# MIT_SRAM.net
KiCad netlist of a schematic drawn in EAGLE
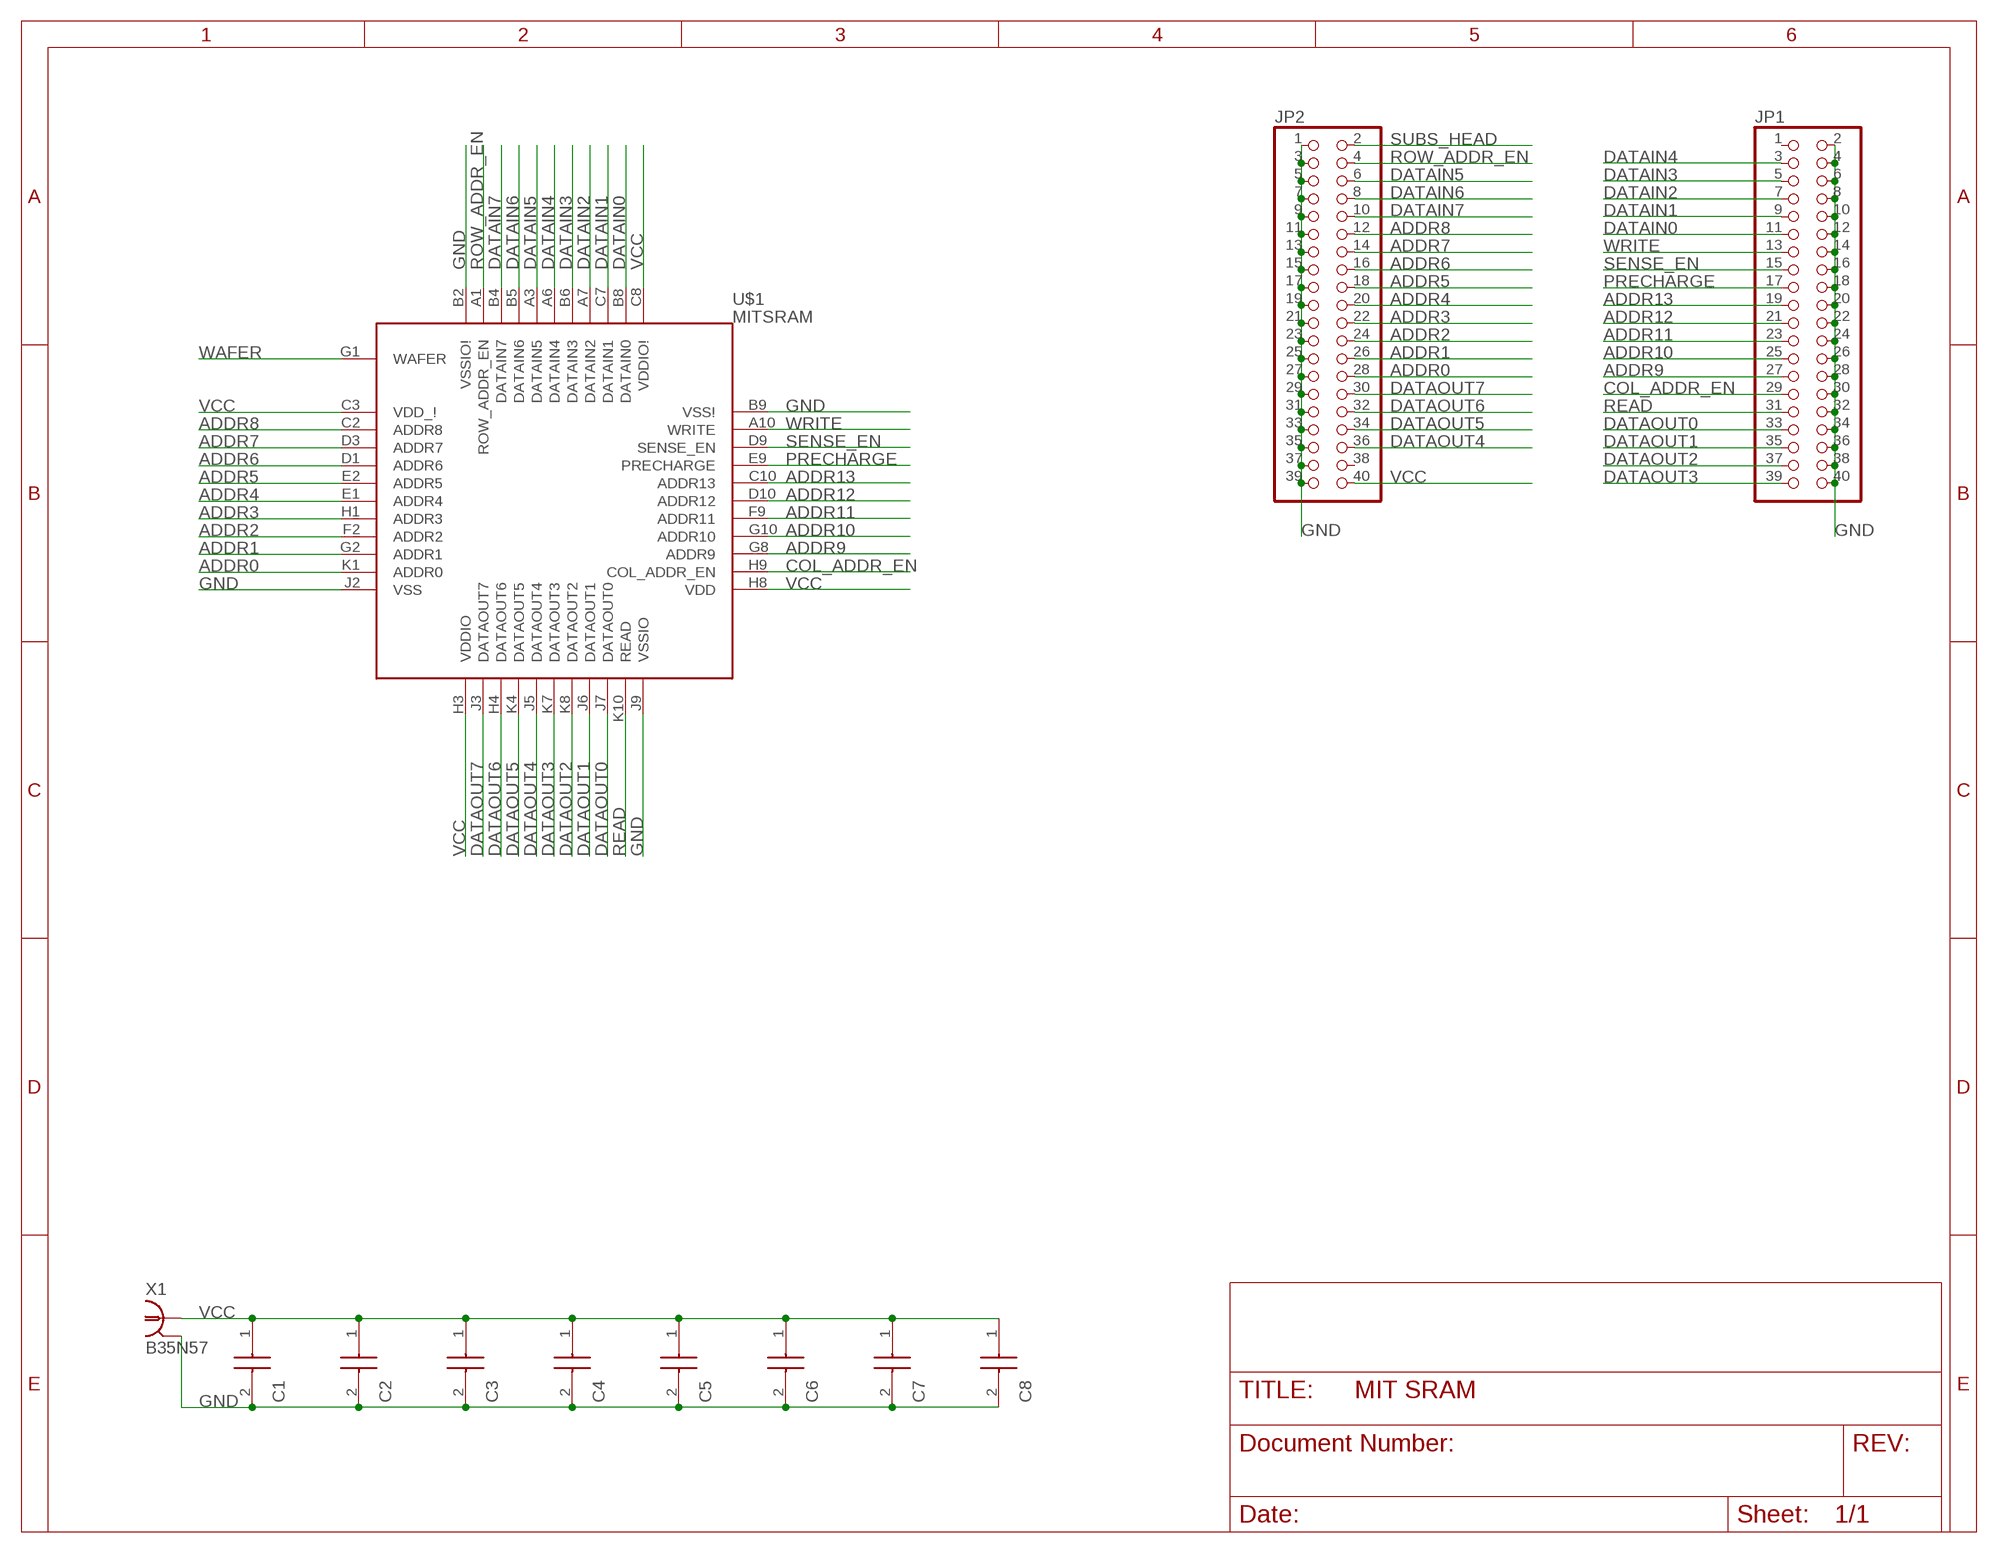
[diagram p0: schematic, sheet 1]

(export (version "E")
  (design (tool "Eeschema 10.0.6"))
  (components
    (comp (ref "C1")
      (value "K104K15X7RF53H5")
      (footprint "eagle-import:K104K15X7RF53H5")
      (fields
        (field (name "MOUSER_PART_NUMBER") "594-K104K15X7RF53H5")
        (field (name "RS_PART_NUMBER") "8523270")
      )
      (libsource (lib "eagle-import") (part "K104K15X7RF53H5"))
    )
    (comp (ref "C2")
      (value "K104K15X7RF53H5")
      (footprint "eagle-import:K104K15X7RF53H5")
      (fields
        (field (name "MOUSER_PART_NUMBER") "594-K104K15X7RF53H5")
        (field (name "RS_PART_NUMBER") "8523270")
      )
      (libsource (lib "eagle-import") (part "K104K15X7RF53H5"))
    )
    (comp (ref "C3")
      (value "K104K15X7RF53H5")
      (footprint "eagle-import:K104K15X7RF53H5")
      (fields
        (field (name "MOUSER_PART_NUMBER") "594-K104K15X7RF53H5")
        (field (name "RS_PART_NUMBER") "8523270")
      )
      (libsource (lib "eagle-import") (part "K104K15X7RF53H5"))
    )
    (comp (ref "C4")
      (value "K104K15X7RF53H5")
      (footprint "eagle-import:K104K15X7RF53H5")
      (fields
        (field (name "MOUSER_PART_NUMBER") "594-K104K15X7RF53H5")
        (field (name "RS_PART_NUMBER") "8523270")
      )
      (libsource (lib "eagle-import") (part "K104K15X7RF53H5"))
    )
    (comp (ref "C5")
      (value "K104K15X7RF53H5")
      (footprint "eagle-import:K104K15X7RF53H5")
      (fields
        (field (name "MOUSER_PART_NUMBER") "594-K104K15X7RF53H5")
        (field (name "RS_PART_NUMBER") "8523270")
      )
      (libsource (lib "eagle-import") (part "K104K15X7RF53H5"))
    )
    (comp (ref "C6")
      (value "K104K15X7RF53H5")
      (footprint "eagle-import:K104K15X7RF53H5")
      (fields
        (field (name "MOUSER_PART_NUMBER") "594-K104K15X7RF53H5")
        (field (name "RS_PART_NUMBER") "8523270")
      )
      (libsource (lib "eagle-import") (part "K104K15X7RF53H5"))
    )
    (comp (ref "C7")
      (value "K104K15X7RF53H5")
      (footprint "eagle-import:K104K15X7RF53H5")
      (fields
        (field (name "MOUSER_PART_NUMBER") "594-K104K15X7RF53H5")
        (field (name "RS_PART_NUMBER") "8523270")
      )
      (libsource (lib "eagle-import") (part "K104K15X7RF53H5"))
    )
    (comp (ref "C8")
      (value "K104K15X7RF53H5")
      (footprint "eagle-import:K104K15X7RF53H5")
      (fields
        (field (name "MOUSER_PART_NUMBER") "594-K104K15X7RF53H5")
        (field (name "RS_PART_NUMBER") "8523270")
      )
      (libsource (lib "eagle-import") (part "K104K15X7RF53H5"))
    )
    (comp (ref "JP1")
      (value "PINHD-2X20")
      (footprint "eagle-import:2X20")
      (libsource (lib "eagle-import") (part "PINHD-2X20"))
    )
    (comp (ref "JP2")
      (value "PINHD-2X20")
      (footprint "eagle-import:2X20")
      (libsource (lib "eagle-import") (part "PINHD-2X20"))
    )
    (comp (ref "U$1")
      (value "MITSRAM")
      (footprint "eagle-import:BGA100C50P10X10_600X600X100N")
      (libsource (lib "eagle-import") (part "MITSRAM"))
    )
    (comp (ref "X1")
      (value "B35N57")
      (footprint "eagle-import:B35N57")
      (libsource (lib "eagle-import") (part "B35N57"))
    )
  )
  (nets
    (net (code "1") (name "/ADDR0") (class "Default")
      (node (ref "JP2") (pin "28") (pinfunction "28_28") (pintype "passive"))
      (node (ref "U$1") (pin "K1") (pinfunction "ADDR0_K1") (pintype "bidirectional"))
    )
    (net (code "2") (name "/ADDR1") (class "Default")
      (node (ref "JP2") (pin "26") (pinfunction "26_26") (pintype "passive"))
      (node (ref "U$1") (pin "G2") (pinfunction "ADDR1_G2") (pintype "bidirectional"))
    )
    (net (code "3") (name "/ADDR2") (class "Default")
      (node (ref "JP2") (pin "24") (pinfunction "24_24") (pintype "passive"))
      (node (ref "U$1") (pin "F2") (pinfunction "ADDR2_F2") (pintype "bidirectional"))
    )
    (net (code "4") (name "/ADDR3") (class "Default")
      (node (ref "JP2") (pin "22") (pinfunction "22_22") (pintype "passive"))
      (node (ref "U$1") (pin "H1") (pinfunction "ADDR3_H1") (pintype "bidirectional"))
    )
    (net (code "5") (name "/ADDR4") (class "Default")
      (node (ref "JP2") (pin "20") (pinfunction "20_20") (pintype "passive"))
      (node (ref "U$1") (pin "E1") (pinfunction "ADDR4_E1") (pintype "bidirectional"))
    )
    (net (code "6") (name "/ADDR5") (class "Default")
      (node (ref "JP2") (pin "18") (pinfunction "18_18") (pintype "passive"))
      (node (ref "U$1") (pin "E2") (pinfunction "ADDR5_E2") (pintype "bidirectional"))
    )
    (net (code "7") (name "/ADDR6") (class "Default")
      (node (ref "JP2") (pin "16") (pinfunction "16_16") (pintype "passive"))
      (node (ref "U$1") (pin "D1") (pinfunction "ADDR6_D1") (pintype "bidirectional"))
    )
    (net (code "8") (name "/ADDR7") (class "Default")
      (node (ref "JP2") (pin "14") (pinfunction "14_14") (pintype "passive"))
      (node (ref "U$1") (pin "D3") (pinfunction "ADDR7_D3") (pintype "bidirectional"))
    )
    (net (code "9") (name "/ADDR8") (class "Default")
      (node (ref "JP2") (pin "12") (pinfunction "12_12") (pintype "passive"))
      (node (ref "U$1") (pin "C2") (pinfunction "ADDR8_C2") (pintype "bidirectional"))
    )
    (net (code "10") (name "/ADDR9") (class "Default")
      (node (ref "JP1") (pin "27") (pinfunction "27_27") (pintype "passive"))
      (node (ref "U$1") (pin "G8") (pinfunction "ADDR9_G8") (pintype "bidirectional"))
    )
    (net (code "11") (name "/ADDR10") (class "Default")
      (node (ref "JP1") (pin "25") (pinfunction "25_25") (pintype "passive"))
      (node (ref "U$1") (pin "G10") (pinfunction "ADDR10_G10") (pintype "bidirectional"))
    )
    (net (code "12") (name "/ADDR11") (class "Default")
      (node (ref "JP1") (pin "23") (pinfunction "23_23") (pintype "passive"))
      (node (ref "U$1") (pin "F9") (pinfunction "ADDR11_F9") (pintype "bidirectional"))
    )
    (net (code "13") (name "/ADDR12") (class "Default")
      (node (ref "JP1") (pin "21") (pinfunction "21_21") (pintype "passive"))
      (node (ref "U$1") (pin "D10") (pinfunction "ADDR12_D10") (pintype "bidirectional"))
    )
    (net (code "14") (name "/ADDR13") (class "Default")
      (node (ref "JP1") (pin "19") (pinfunction "19_19") (pintype "passive"))
      (node (ref "U$1") (pin "C10") (pinfunction "ADDR13_C10") (pintype "bidirectional"))
    )
    (net (code "15") (name "/COL_ADDR_EN") (class "Default")
      (node (ref "JP1") (pin "29") (pinfunction "29_29") (pintype "passive"))
      (node (ref "U$1") (pin "H9") (pinfunction "COL_ADDR_EN_H9") (pintype "bidirectional"))
    )
    (net (code "16") (name "/DATAIN0") (class "Default")
      (node (ref "JP1") (pin "11") (pinfunction "11_11") (pintype "passive"))
      (node (ref "U$1") (pin "B8") (pinfunction "DATAIN0_B8") (pintype "bidirectional"))
    )
    (net (code "17") (name "/DATAIN1") (class "Default")
      (node (ref "JP1") (pin "9") (pinfunction "9_9") (pintype "passive"))
      (node (ref "U$1") (pin "C7") (pinfunction "DATAIN1_C7") (pintype "bidirectional"))
    )
    (net (code "18") (name "/DATAIN2") (class "Default")
      (node (ref "JP1") (pin "7") (pinfunction "7_7") (pintype "passive"))
      (node (ref "U$1") (pin "A7") (pinfunction "DATAIN2_A7") (pintype "bidirectional"))
    )
    (net (code "19") (name "/DATAIN3") (class "Default")
      (node (ref "JP1") (pin "5") (pinfunction "5_5") (pintype "passive"))
      (node (ref "U$1") (pin "B6") (pinfunction "DATAIN3_B6") (pintype "bidirectional"))
    )
    (net (code "20") (name "/DATAIN4") (class "Default")
      (node (ref "JP1") (pin "3") (pinfunction "3_3") (pintype "passive"))
      (node (ref "U$1") (pin "A6") (pinfunction "DATAIN4_A6") (pintype "bidirectional"))
    )
    (net (code "21") (name "/DATAIN5") (class "Default")
      (node (ref "JP2") (pin "6") (pinfunction "6_6") (pintype "passive"))
      (node (ref "U$1") (pin "A3") (pinfunction "DATAIN5_A3") (pintype "bidirectional"))
    )
    (net (code "22") (name "/DATAIN6") (class "Default")
      (node (ref "JP2") (pin "8") (pinfunction "8_8") (pintype "passive"))
      (node (ref "U$1") (pin "B5") (pinfunction "DATAIN6_B5") (pintype "bidirectional"))
    )
    (net (code "23") (name "/DATAIN7") (class "Default")
      (node (ref "JP2") (pin "10") (pinfunction "10_10") (pintype "passive"))
      (node (ref "U$1") (pin "B4") (pinfunction "DATAIN7_B4") (pintype "bidirectional"))
    )
    (net (code "24") (name "/DATAOUT0") (class "Default")
      (node (ref "JP1") (pin "33") (pinfunction "33_33") (pintype "passive"))
      (node (ref "U$1") (pin "J7") (pinfunction "DATAOUT0_J7") (pintype "bidirectional"))
    )
    (net (code "25") (name "/DATAOUT1") (class "Default")
      (node (ref "JP1") (pin "35") (pinfunction "35_35") (pintype "passive"))
      (node (ref "U$1") (pin "J6") (pinfunction "DATAOUT1_J6") (pintype "bidirectional"))
    )
    (net (code "26") (name "/DATAOUT2") (class "Default")
      (node (ref "JP1") (pin "37") (pinfunction "37_37") (pintype "passive"))
      (node (ref "U$1") (pin "K8") (pinfunction "DATAOUT2_K8") (pintype "bidirectional"))
    )
    (net (code "27") (name "/DATAOUT3") (class "Default")
      (node (ref "JP1") (pin "39") (pinfunction "39_39") (pintype "passive"))
      (node (ref "U$1") (pin "K7") (pinfunction "DATAOUT3_K7") (pintype "bidirectional"))
    )
    (net (code "28") (name "/DATAOUT4") (class "Default")
      (node (ref "JP2") (pin "36") (pinfunction "36_36") (pintype "passive"))
      (node (ref "U$1") (pin "J5") (pinfunction "DATAOUT4_J5") (pintype "bidirectional"))
    )
    (net (code "29") (name "/DATAOUT5") (class "Default")
      (node (ref "JP2") (pin "34") (pinfunction "34_34") (pintype "passive"))
      (node (ref "U$1") (pin "K4") (pinfunction "DATAOUT5_K4") (pintype "bidirectional"))
    )
    (net (code "30") (name "/DATAOUT6") (class "Default")
      (node (ref "JP2") (pin "32") (pinfunction "32_32") (pintype "passive"))
      (node (ref "U$1") (pin "H4") (pinfunction "DATAOUT6_H4") (pintype "bidirectional"))
    )
    (net (code "31") (name "/DATAOUT7") (class "Default")
      (node (ref "JP2") (pin "30") (pinfunction "30_30") (pintype "passive"))
      (node (ref "U$1") (pin "J3") (pinfunction "DATAOUT7_J3") (pintype "bidirectional"))
    )
    (net (code "32") (name "/GND") (class "Default")
      (node (ref "C1") (pin "2") (pinfunction "2_2") (pintype "bidirectional"))
      (node (ref "C2") (pin "2") (pinfunction "2_2") (pintype "bidirectional"))
      (node (ref "C3") (pin "2") (pinfunction "2_2") (pintype "bidirectional"))
      (node (ref "C4") (pin "2") (pinfunction "2_2") (pintype "bidirectional"))
      (node (ref "C5") (pin "2") (pinfunction "2_2") (pintype "bidirectional"))
      (node (ref "C6") (pin "2") (pinfunction "2_2") (pintype "bidirectional"))
      (node (ref "C7") (pin "2") (pinfunction "2_2") (pintype "bidirectional"))
      (node (ref "C8") (pin "2") (pinfunction "2_2") (pintype "bidirectional"))
      (node (ref "JP1") (pin "10") (pinfunction "10_10") (pintype "passive"))
      (node (ref "JP1") (pin "12") (pinfunction "12_12") (pintype "passive"))
      (node (ref "JP1") (pin "14") (pinfunction "14_14") (pintype "passive"))
      (node (ref "JP1") (pin "16") (pinfunction "16_16") (pintype "passive"))
      (node (ref "JP1") (pin "18") (pinfunction "18_18") (pintype "passive"))
      (node (ref "JP1") (pin "2") (pinfunction "2_2") (pintype "passive"))
      (node (ref "JP1") (pin "20") (pinfunction "20_20") (pintype "passive"))
      (node (ref "JP1") (pin "22") (pinfunction "22_22") (pintype "passive"))
      (node (ref "JP1") (pin "24") (pinfunction "24_24") (pintype "passive"))
      (node (ref "JP1") (pin "26") (pinfunction "26_26") (pintype "passive"))
      (node (ref "JP1") (pin "28") (pinfunction "28_28") (pintype "passive"))
      (node (ref "JP1") (pin "30") (pinfunction "30_30") (pintype "passive"))
      (node (ref "JP1") (pin "32") (pinfunction "32_32") (pintype "passive"))
      (node (ref "JP1") (pin "34") (pinfunction "34_34") (pintype "passive"))
      (node (ref "JP1") (pin "36") (pinfunction "36_36") (pintype "passive"))
      (node (ref "JP1") (pin "38") (pinfunction "38_38") (pintype "passive"))
      (node (ref "JP1") (pin "4") (pinfunction "4_4") (pintype "passive"))
      (node (ref "JP1") (pin "40") (pinfunction "40_40") (pintype "passive"))
      (node (ref "JP1") (pin "6") (pinfunction "6_6") (pintype "passive"))
      (node (ref "JP1") (pin "8") (pinfunction "8_8") (pintype "passive"))
      (node (ref "JP2") (pin "1") (pinfunction "1_1") (pintype "passive"))
      (node (ref "JP2") (pin "11") (pinfunction "11_11") (pintype "passive"))
      (node (ref "JP2") (pin "13") (pinfunction "13_13") (pintype "passive"))
      (node (ref "JP2") (pin "15") (pinfunction "15_15") (pintype "passive"))
      (node (ref "JP2") (pin "17") (pinfunction "17_17") (pintype "passive"))
      (node (ref "JP2") (pin "19") (pinfunction "19_19") (pintype "passive"))
      (node (ref "JP2") (pin "21") (pinfunction "21_21") (pintype "passive"))
      (node (ref "JP2") (pin "23") (pinfunction "23_23") (pintype "passive"))
      (node (ref "JP2") (pin "25") (pinfunction "25_25") (pintype "passive"))
      (node (ref "JP2") (pin "27") (pinfunction "27_27") (pintype "passive"))
      (node (ref "JP2") (pin "29") (pinfunction "29_29") (pintype "passive"))
      (node (ref "JP2") (pin "3") (pinfunction "3_3") (pintype "passive"))
      (node (ref "JP2") (pin "31") (pinfunction "31_31") (pintype "passive"))
      (node (ref "JP2") (pin "33") (pinfunction "33_33") (pintype "passive"))
      (node (ref "JP2") (pin "35") (pinfunction "35_35") (pintype "passive"))
      (node (ref "JP2") (pin "37") (pinfunction "37_37") (pintype "passive"))
      (node (ref "JP2") (pin "39") (pinfunction "39_39") (pintype "passive"))
      (node (ref "JP2") (pin "5") (pinfunction "5_5") (pintype "passive"))
      (node (ref "JP2") (pin "7") (pinfunction "7_7") (pintype "passive"))
      (node (ref "JP2") (pin "9") (pinfunction "9_9") (pintype "passive"))
      (node (ref "U$1") (pin "B2") (pinfunction "VSSIO~{}_B2") (pintype "bidirectional"))
      (node (ref "U$1") (pin "B9") (pinfunction "VSS~{}_B9") (pintype "bidirectional"))
      (node (ref "U$1") (pin "J2") (pinfunction "VSS_J2") (pintype "bidirectional"))
      (node (ref "U$1") (pin "J9") (pinfunction "VSSIO_J9") (pintype "bidirectional"))
      (node (ref "X1") (pin "2") (pinfunction "2_2") (pintype "passive"))
      (node (ref "X1") (pin "3") (pinfunction "2_3") (pintype "passive"))
      (node (ref "X1") (pin "4") (pinfunction "2_4") (pintype "passive"))
      (node (ref "X1") (pin "5") (pinfunction "2_5") (pintype "passive"))
    )
    (net (code "33") (name "/PRECHARGE") (class "Default")
      (node (ref "JP1") (pin "17") (pinfunction "17_17") (pintype "passive"))
      (node (ref "U$1") (pin "E9") (pinfunction "PRECHARGE_E9") (pintype "bidirectional"))
    )
    (net (code "34") (name "/READ") (class "Default")
      (node (ref "JP1") (pin "31") (pinfunction "31_31") (pintype "passive"))
      (node (ref "U$1") (pin "K10") (pinfunction "READ_K10") (pintype "bidirectional"))
    )
    (net (code "35") (name "/ROW_ADDR_EN") (class "Default")
      (node (ref "JP2") (pin "4") (pinfunction "4_4") (pintype "passive"))
      (node (ref "U$1") (pin "A1") (pinfunction "ROW_ADDR_EN_A1") (pintype "bidirectional"))
    )
    (net (code "36") (name "/SENSE_EN") (class "Default")
      (node (ref "JP1") (pin "15") (pinfunction "15_15") (pintype "passive"))
      (node (ref "U$1") (pin "D9") (pinfunction "SENSE_EN_D9") (pintype "bidirectional"))
    )
    (net (code "37") (name "/SUBS_HEAD") (class "Default")
      (node (ref "JP2") (pin "2") (pinfunction "2_2") (pintype "passive"))
    )
    (net (code "38") (name "/VCC") (class "Default")
      (node (ref "C1") (pin "1") (pinfunction "1_1") (pintype "bidirectional"))
      (node (ref "C2") (pin "1") (pinfunction "1_1") (pintype "bidirectional"))
      (node (ref "C3") (pin "1") (pinfunction "1_1") (pintype "bidirectional"))
      (node (ref "C4") (pin "1") (pinfunction "1_1") (pintype "bidirectional"))
      (node (ref "C5") (pin "1") (pinfunction "1_1") (pintype "bidirectional"))
      (node (ref "C6") (pin "1") (pinfunction "1_1") (pintype "bidirectional"))
      (node (ref "C7") (pin "1") (pinfunction "1_1") (pintype "bidirectional"))
      (node (ref "C8") (pin "1") (pinfunction "1_1") (pintype "bidirectional"))
      (node (ref "JP2") (pin "40") (pinfunction "40_40") (pintype "passive"))
      (node (ref "U$1") (pin "C3") (pinfunction "VDD_~{}_C3") (pintype "bidirectional"))
      (node (ref "U$1") (pin "C8") (pinfunction "VDDIO~{}_C8") (pintype "bidirectional"))
      (node (ref "U$1") (pin "H3") (pinfunction "VDDIO_H3") (pintype "bidirectional"))
      (node (ref "U$1") (pin "H8") (pinfunction "VDD_H8") (pintype "bidirectional"))
      (node (ref "X1") (pin "1") (pinfunction "1_1") (pintype "passive"))
    )
    (net (code "39") (name "/WAFER") (class "Default")
      (node (ref "U$1") (pin "G1") (pinfunction "WAFER_G1") (pintype "bidirectional"))
    )
    (net (code "40") (name "/WRITE") (class "Default")
      (node (ref "JP1") (pin "13") (pinfunction "13_13") (pintype "passive"))
      (node (ref "U$1") (pin "A10") (pinfunction "WRITE_A10") (pintype "bidirectional"))
    )
    (net (code "41") (name "unconnected-(JP1-Pad1)") (class "Default")
      (node (ref "JP1") (pin "1") (pinfunction "1_1") (pintype "passive"))
    )
    (net (code "42") (name "unconnected-(JP2-Pad38)") (class "Default")
      (node (ref "JP2") (pin "38") (pinfunction "38_38") (pintype "passive"))
    )
  )
)
